# TPA3126.net
KiCad netlist of a schematic drawn in Altium Designer
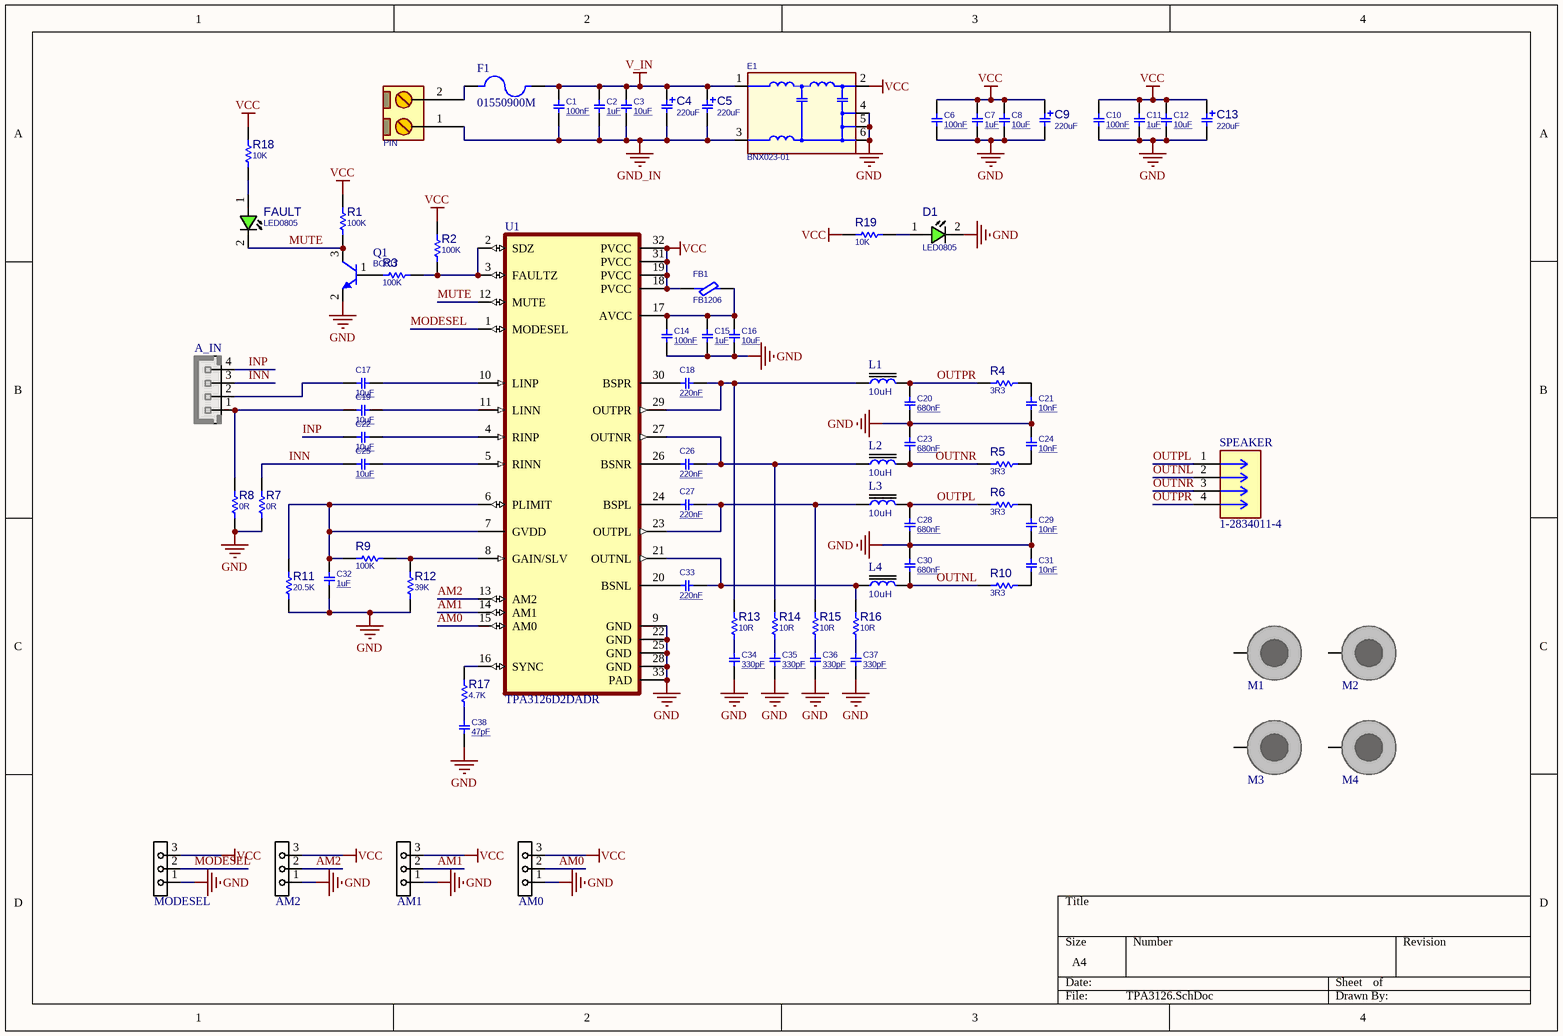
[diagram p0: TPA3126.SchDoc]

(export (version "E")
  (design (tool "Eeschema 10.0.6"))
  (components
    (comp (ref "AM0")
      (value "JMPHDR3PIN")
      (footprint "JP_3_60W")
      (description "JUMPER, HEADER 3PIN")
      (fields (field (name "MANF") "MANF") (field (name "MANF_P#") "MANF_P#"))
      (libsource (lib "test-tp_jumper") (part "JUMPER_SOLDER_3P"))
    )
    (comp (ref "AM1")
      (value "JMPHDR3PIN")
      (footprint "JP_3_60W")
      (description "JUMPER, HEADER 3PIN")
      (fields (field (name "MANF") "MANF") (field (name "MANF_P#") "MANF_P#"))
      (libsource (lib "test-tp_jumper") (part "JUMPER_SOLDER_3P"))
    )
    (comp (ref "AM2")
      (value "JMPHDR3PIN")
      (footprint "JP_3_60W")
      (description "JUMPER, HEADER 3PIN")
      (fields (field (name "MANF") "MANF") (field (name "MANF_P#") "MANF_P#"))
      (libsource (lib "test-tp_jumper") (part "JUMPER_SOLDER_3P"))
    )
    (comp (ref "A_IN")
      (value "HHDR_4")
      (footprint "XH_4")
      (description "JST-XH pitch: 2.5mm")
      (libsource (lib "conn_wire2board") (part "XH_4"))
    )
    (comp (ref "C1")
      (value "100nF")
      (footprint "C0805")
      (description "CAP, MLCC, 100nF, 50V, C0G, 10%, 0402")
      (fields (field (name "MANF_P#") "MANF_PART#") (field (name "MANF") "Murata"))
      (libsource (lib "passive_smd") (part "CAP_SMD_MLCC"))
    )
    (comp (ref "C2")
      (value "1uF")
      (footprint "C0805")
      (description "CAP, MLCC, 1uF, 50V, C0G, 10%, 0402")
      (fields (field (name "MANF_P#") "MANF_PART#") (field (name "MANF") "Murata"))
      (libsource (lib "passive_smd") (part "CAP_SMD_MLCC"))
    )
    (comp (ref "C3")
      (value "10uF")
      (footprint "C0805")
      (description "CAP, MLCC, 10uF, 50V, C0G, 10%, 0402")
      (fields (field (name "MANF_P#") "MANF_PART#") (field (name "MANF") "Murata"))
      (libsource (lib "passive_smd") (part "CAP_SMD_MLCC"))
    )
    (comp (ref "C4")
      (value "220uF")
      (footprint "C_EL_8X12")
      (description "CAP, THD, ELEC,")
      (fields (field (name "MANF_P#") "MANF_PART#") (field (name "MANF") "MANF"))
      (libsource (lib "passive_thd") (part "CAP_THD_EL"))
    )
    (comp (ref "C5")
      (value "220uF")
      (footprint "C_EL_8X12")
      (description "CAP, THD, ELEC,")
      (fields (field (name "MANF_P#") "MANF_PART#") (field (name "MANF") "MANF"))
      (libsource (lib "passive_thd") (part "CAP_THD_EL"))
    )
    (comp (ref "C6")
      (value "100nF")
      (footprint "C0805")
      (description "CAP, MLCC, 100nF, 50V, C0G, 10%, 0402")
      (fields (field (name "MANF_P#") "MANF_PART#") (field (name "MANF") "Murata"))
      (libsource (lib "passive_smd") (part "CAP_SMD_MLCC"))
    )
    (comp (ref "C7")
      (value "1uF")
      (footprint "C0805")
      (description "CAP, MLCC, 1uF, 50V, C0G, 10%, 0402")
      (fields (field (name "MANF_P#") "MANF_PART#") (field (name "MANF") "Murata"))
      (libsource (lib "passive_smd") (part "CAP_SMD_MLCC"))
    )
    (comp (ref "C8")
      (value "10uF")
      (footprint "C0805")
      (description "CAP, MLCC, 10uF, 50V, C0G, 10%, 0402")
      (fields (field (name "MANF_P#") "MANF_PART#") (field (name "MANF") "Murata"))
      (libsource (lib "passive_smd") (part "CAP_SMD_MLCC"))
    )
    (comp (ref "C9")
      (value "220uF")
      (footprint "C_EL_8X12")
      (description "CAP, THD, ELEC,")
      (fields (field (name "MANF_P#") "MANF_PART#") (field (name "MANF") "MANF"))
      (libsource (lib "passive_thd") (part "CAP_THD_EL"))
    )
    (comp (ref "C10")
      (value "100nF")
      (footprint "C0805")
      (description "CAP, MLCC, 100nF, 50V, C0G, 10%, 0402")
      (fields (field (name "MANF_P#") "MANF_PART#") (field (name "MANF") "Murata"))
      (libsource (lib "passive_smd") (part "CAP_SMD_MLCC"))
    )
    (comp (ref "C11")
      (value "1uF")
      (footprint "C0805")
      (description "CAP, MLCC, 1uF, 50V, C0G, 10%, 0402")
      (fields (field (name "MANF_P#") "MANF_PART#") (field (name "MANF") "Murata"))
      (libsource (lib "passive_smd") (part "CAP_SMD_MLCC"))
    )
    (comp (ref "C12")
      (value "10uF")
      (footprint "C0805")
      (description "CAP, MLCC, 10uF, 50V, C0G, 10%, 0402")
      (fields (field (name "MANF_P#") "MANF_PART#") (field (name "MANF") "Murata"))
      (libsource (lib "passive_smd") (part "CAP_SMD_MLCC"))
    )
    (comp (ref "C13")
      (value "220uF")
      (footprint "C_EL_8X12")
      (description "CAP, THD, ELEC,")
      (fields (field (name "MANF_P#") "MANF_PART#") (field (name "MANF") "MANF"))
      (libsource (lib "passive_thd") (part "CAP_THD_EL"))
    )
    (comp (ref "C14")
      (value "100nF")
      (footprint "C0805")
      (description "CAP, MLCC, 100nF, 50V, C0G, 10%, 0402")
      (fields (field (name "MANF_P#") "MANF_PART#") (field (name "MANF") "Murata"))
      (libsource (lib "passive_smd") (part "CAP_SMD_MLCC"))
    )
    (comp (ref "C15")
      (value "1uF")
      (footprint "C0805")
      (description "CAP, MLCC, 1uF, 50V, C0G, 10%, 0402")
      (fields (field (name "MANF_P#") "MANF_PART#") (field (name "MANF") "Murata"))
      (libsource (lib "passive_smd") (part "CAP_SMD_MLCC"))
    )
    (comp (ref "C16")
      (value "10uF")
      (footprint "C0805")
      (description "CAP, MLCC, 10uF, 50V, C0G, 10%, 0402")
      (fields (field (name "MANF_P#") "MANF_PART#") (field (name "MANF") "Murata"))
      (libsource (lib "passive_smd") (part "CAP_SMD_MLCC"))
    )
    (comp (ref "C17")
      (value "10uF")
      (footprint "C0805")
      (description "CAP, MLCC, 10uF, 50V, C0G, 10%, 0402")
      (fields (field (name "MANF_P#") "MANF_PART#") (field (name "MANF") "Murata"))
      (libsource (lib "passive_smd") (part "CAP_SMD_MLCC"))
    )
    (comp (ref "C18")
      (value "220nF")
      (footprint "C0603")
      (description "CAP, MLCC, 220nF, 50V, C0G, 10%, 0402")
      (fields (field (name "MANF_P#") "MANF_PART#") (field (name "MANF") "Murata"))
      (libsource (lib "passive_smd") (part "CAP_SMD_MLCC"))
    )
    (comp (ref "C19")
      (value "10uF")
      (footprint "C0805")
      (description "CAP, MLCC, 10uF, 50V, C0G, 10%, 0402")
      (fields (field (name "MANF_P#") "MANF_PART#") (field (name "MANF") "Murata"))
      (libsource (lib "passive_smd") (part "CAP_SMD_MLCC"))
    )
    (comp (ref "C20")
      (value "680nF")
      (footprint "C0805")
      (description "CAP, MLCC, 650nF, 50V, C0G, 10%, 0402")
      (fields (field (name "MANF_P#") "MANF_PART#") (field (name "MANF") "Murata"))
      (libsource (lib "passive_smd") (part "CAP_SMD_MLCC"))
    )
    (comp (ref "C21")
      (value "10nF")
      (footprint "C0805")
      (description "CAP, MLCC, 10nF, 50V, C0G, 10%, 0402")
      (fields (field (name "MANF_P#") "MANF_PART#") (field (name "MANF") "Murata"))
      (libsource (lib "passive_smd") (part "CAP_SMD_MLCC"))
    )
    (comp (ref "C22")
      (value "10uF")
      (footprint "C0805")
      (description "CAP, MLCC, 10uF, 50V, C0G, 10%, 0402")
      (fields (field (name "MANF_P#") "MANF_PART#") (field (name "MANF") "Murata"))
      (libsource (lib "passive_smd") (part "CAP_SMD_MLCC"))
    )
    (comp (ref "C23")
      (value "680nF")
      (footprint "C0805")
      (description "CAP, MLCC, 650nF, 50V, C0G, 10%, 0402")
      (fields (field (name "MANF_P#") "MANF_PART#") (field (name "MANF") "Murata"))
      (libsource (lib "passive_smd") (part "CAP_SMD_MLCC"))
    )
    (comp (ref "C24")
      (value "10nF")
      (footprint "C0805")
      (description "CAP, MLCC, 10nF, 50V, C0G, 10%, 0402")
      (fields (field (name "MANF_P#") "MANF_PART#") (field (name "MANF") "Murata"))
      (libsource (lib "passive_smd") (part "CAP_SMD_MLCC"))
    )
    (comp (ref "C25")
      (value "10uF")
      (footprint "C0805")
      (description "CAP, MLCC, 10uF, 50V, C0G, 10%, 0402")
      (fields (field (name "MANF_P#") "MANF_PART#") (field (name "MANF") "Murata"))
      (libsource (lib "passive_smd") (part "CAP_SMD_MLCC"))
    )
    (comp (ref "C26")
      (value "220nF")
      (footprint "C0603")
      (description "CAP, MLCC, 220nF, 50V, C0G, 10%, 0402")
      (fields (field (name "MANF_P#") "MANF_PART#") (field (name "MANF") "Murata"))
      (libsource (lib "passive_smd") (part "CAP_SMD_MLCC"))
    )
    (comp (ref "C27")
      (value "220nF")
      (footprint "C0603")
      (description "CAP, MLCC, 220nF, 50V, C0G, 10%, 0402")
      (fields (field (name "MANF_P#") "MANF_PART#") (field (name "MANF") "Murata"))
      (libsource (lib "passive_smd") (part "CAP_SMD_MLCC"))
    )
    (comp (ref "C28")
      (value "680nF")
      (footprint "C0805")
      (description "CAP, MLCC, 650nF, 50V, C0G, 10%, 0402")
      (fields (field (name "MANF_P#") "MANF_PART#") (field (name "MANF") "Murata"))
      (libsource (lib "passive_smd") (part "CAP_SMD_MLCC"))
    )
    (comp (ref "C29")
      (value "10nF")
      (footprint "C0805")
      (description "CAP, MLCC, 10nF, 50V, C0G, 10%, 0402")
      (fields (field (name "MANF_P#") "MANF_PART#") (field (name "MANF") "Murata"))
      (libsource (lib "passive_smd") (part "CAP_SMD_MLCC"))
    )
    (comp (ref "C30")
      (value "680nF")
      (footprint "C0805")
      (description "CAP, MLCC, 650nF, 50V, C0G, 10%, 0402")
      (fields (field (name "MANF_P#") "MANF_PART#") (field (name "MANF") "Murata"))
      (libsource (lib "passive_smd") (part "CAP_SMD_MLCC"))
    )
    (comp (ref "C31")
      (value "10nF")
      (footprint "C0805")
      (description "CAP, MLCC, 10nF, 50V, C0G, 10%, 0402")
      (fields (field (name "MANF_P#") "MANF_PART#") (field (name "MANF") "Murata"))
      (libsource (lib "passive_smd") (part "CAP_SMD_MLCC"))
    )
    (comp (ref "C32")
      (value "1uF")
      (footprint "C0805")
      (description "CAP, MLCC, 1uF, 50V, C0G, 10%, 0402")
      (fields (field (name "MANF_P#") "MANF_PART#") (field (name "MANF") "Murata"))
      (libsource (lib "passive_smd") (part "CAP_SMD_MLCC"))
    )
    (comp (ref "C33")
      (value "220nF")
      (footprint "C0603")
      (description "CAP, MLCC, 220nF, 50V, C0G, 10%, 0402")
      (fields (field (name "MANF_P#") "MANF_PART#") (field (name "MANF") "Murata"))
      (libsource (lib "passive_smd") (part "CAP_SMD_MLCC"))
    )
    (comp (ref "C34")
      (value "330pF")
      (footprint "C0805")
      (description "CAP, MLCC, 330pF, 50V, C0G, 10%, 0402")
      (fields (field (name "MANF_P#") "MANF_PART#") (field (name "MANF") "Murata"))
      (libsource (lib "passive_smd") (part "CAP_SMD_MLCC"))
    )
    (comp (ref "C35")
      (value "330pF")
      (footprint "C0805")
      (description "CAP, MLCC, 330pF, 50V, C0G, 10%, 0402")
      (fields (field (name "MANF_P#") "MANF_PART#") (field (name "MANF") "Murata"))
      (libsource (lib "passive_smd") (part "CAP_SMD_MLCC"))
    )
    (comp (ref "C36")
      (value "330pF")
      (footprint "C0805")
      (description "CAP, MLCC, 330pF, 50V, C0G, 10%, 0402")
      (fields (field (name "MANF_P#") "MANF_PART#") (field (name "MANF") "Murata"))
      (libsource (lib "passive_smd") (part "CAP_SMD_MLCC"))
    )
    (comp (ref "C37")
      (value "330pF")
      (footprint "C0805")
      (description "CAP, MLCC, 330pF, 50V, C0G, 10%, 0402")
      (fields (field (name "MANF_P#") "MANF_PART#") (field (name "MANF") "Murata"))
      (libsource (lib "passive_smd") (part "CAP_SMD_MLCC"))
    )
    (comp (ref "C38")
      (value "47pF")
      (footprint "C0805")
      (description "CAP, MLCC, 47pF, 50V, C0G, 10%, 0402")
      (fields (field (name "MANF_P#") "MANF_PART#") (field (name "MANF") "Murata"))
      (libsource (lib "passive_smd") (part "CAP_SMD_MLCC"))
    )
    (comp (ref "D1")
      (value "LED0805")
      (footprint "LED0805")
      (description "LED, SMD, 0805 red")
      (fields (field (name "MANF") "MANF") (field (name "MANF_P#") "MANF_PART#"))
      (libsource (lib "led(diode)") (part "LED_SMD_0805"))
    )
    (comp (ref "E1")
      (value "BNX023-01")
      (footprint "BNX02")
      (description "EMIFIL, BLOCK TYPE,")
      (fields (field (name "MANF") "Murata") (field (name "MANF_1") "MURATA"))
      (libsource (lib "emi_filter") (part "BNX023-01"))
    )
    (comp (ref "F1")
      (value "01550900M")
      (footprint "FUSE_01550900M")
      (description "Fuse Block, Cartridge, OMNI-BLOK Series, 125V, 10A, J-Lead ¦ Littelfuse 01550900M")
      (fields (field (name "MF") "Littelfuse Inc."))
      (libsource (lib "01550900M") (part "01550900M"))
    )
    (comp (ref "FAULT")
      (value "LED0805")
      (footprint "LED0805")
      (description "LED, SMD, 0805 red")
      (fields (field (name "MANF") "MANF") (field (name "MANF_P#") "MANF_PART#"))
      (libsource (lib "led(diode)") (part "LED_SMD_0805"))
    )
    (comp (ref "FB1")
      (value "FB1206")
      (footprint "L1206")
      (description "FERRITE_Bead, SMD")
      (fields (field (name "MANF") "MURATA") (field (name "MANF_P#") "BLM15AG121SN1D"))
      (libsource (lib "emi_filter") (part "FBEAD_SMD"))
    )
    (comp (ref "L1")
      (value "10uH")
      (footprint "L_12")
      (description "INDUCTOR, POWER, SMD")
      (libsource (lib "inductor_power") (part "INDPWR_SMD"))
    )
    (comp (ref "L2")
      (value "10uH")
      (footprint "L_12")
      (description "INDUCTOR, POWER, SMD")
      (libsource (lib "inductor_power") (part "INDPWR_SMD"))
    )
    (comp (ref "L3")
      (value "10uH")
      (footprint "L_12")
      (description "INDUCTOR, POWER, SMD")
      (libsource (lib "inductor_power") (part "INDPWR_SMD"))
    )
    (comp (ref "L4")
      (value "10uH")
      (footprint "L_12")
      (description "INDUCTOR, POWER, SMD")
      (libsource (lib "inductor_power") (part "INDPWR_SMD"))
    )
    (comp (ref "M1")
      (value "DNP/MH")
      (footprint "SCMH_M3P5FT")
      (description "SCREW mouting, M3.5, 3.5mm diameter and 7.0mm, FlatHead")
      (libsource (lib "mech_mountingHole") (part "SCMH_M3P5FT"))
    )
    (comp (ref "M2")
      (value "DNP/MH")
      (footprint "SCMH_M3P5FT")
      (description "SCREW mouting, M3.5, 3.5mm diameter and 7.0mm, FlatHead")
      (libsource (lib "mech_mountingHole") (part "SCMH_M3P5FT"))
    )
    (comp (ref "M3")
      (value "DNP/MH")
      (footprint "SCMH_M3P5FT")
      (description "SCREW mouting, M3.5, 3.5mm diameter and 7.0mm, FlatHead")
      (libsource (lib "mech_mountingHole") (part "SCMH_M3P5FT"))
    )
    (comp (ref "M4")
      (value "DNP/MH")
      (footprint "SCMH_M3P5FT")
      (description "SCREW mouting, M3.5, 3.5mm diameter and 7.0mm, FlatHead")
      (libsource (lib "mech_mountingHole") (part "SCMH_M3P5FT"))
    )
    (comp (ref "MODESEL")
      (value "JMPHDR3PIN")
      (footprint "JP_3_60W")
      (description "JUMPER, HEADER 3PIN")
      (fields (field (name "MANF") "MANF") (field (name "MANF_P#") "MANF_P#"))
      (libsource (lib "test-tp_jumper") (part "JUMPER_SOLDER_3P"))
    )
    (comp (ref "PIN")
      (value "CONN_TB2")
      (footprint "MSTB_2")
      (description "CONN, PHOENIX MSTB, 5-G, 5.08mm pitch")
      (libsource (lib "conn_power_terminalB") (part "CONN_MSTB_2"))
    )
    (comp (ref "Q1")
      (value "BC817")
      (footprint "SOT23_3")
      (description "BJT, NPN, 45v, 0.5A, SMD, SOT23")
      (fields (field (name "MANF") "NXP, ON"))
      (libsource (lib "transistor_bjt") (part "NPN_BC817_SOT23"))
    )
    (comp (ref "R1")
      (value "100K")
      (footprint "R0805")
      (description "RESISTOR, SMD")
      (libsource (lib "passive_smd") (part "RES_SMD"))
    )
    (comp (ref "R2")
      (value "100K")
      (footprint "R0805")
      (description "RESISTOR, SMD")
      (libsource (lib "passive_smd") (part "RES_SMD"))
    )
    (comp (ref "R3")
      (value "100K")
      (footprint "R0805")
      (description "RESISTOR, SMD")
      (libsource (lib "passive_smd") (part "RES_SMD"))
    )
    (comp (ref "R4")
      (value "3R3")
      (footprint "R0805")
      (description "RESISTOR, SMD")
      (libsource (lib "passive_smd") (part "RES_SMD"))
    )
    (comp (ref "R5")
      (value "3R3")
      (footprint "R0805")
      (description "RESISTOR, SMD")
      (libsource (lib "passive_smd") (part "RES_SMD"))
    )
    (comp (ref "R6")
      (value "3R3")
      (footprint "R0805")
      (description "RESISTOR, SMD")
      (libsource (lib "passive_smd") (part "RES_SMD"))
    )
    (comp (ref "R7")
      (value "0R")
      (footprint "R0805")
      (description "RESISTOR, SMD")
      (libsource (lib "passive_smd") (part "RES_SMD"))
    )
    (comp (ref "R8")
      (value "0R")
      (footprint "R0805")
      (description "RESISTOR, SMD")
      (libsource (lib "passive_smd") (part "RES_SMD"))
    )
    (comp (ref "R9")
      (value "100K")
      (footprint "R0805")
      (description "RESISTOR, SMD")
      (libsource (lib "passive_smd") (part "RES_SMD"))
    )
    (comp (ref "R10")
      (value "3R3")
      (footprint "R0805")
      (description "RESISTOR, SMD")
      (libsource (lib "passive_smd") (part "RES_SMD"))
    )
    (comp (ref "R11")
      (value "20.5K")
      (footprint "R0805")
      (description "RESISTOR, SMD")
      (libsource (lib "passive_smd") (part "RES_SMD"))
    )
    (comp (ref "R12")
      (value "39K")
      (footprint "R0805")
      (description "RESISTOR, SMD")
      (libsource (lib "passive_smd") (part "RES_SMD"))
    )
    (comp (ref "R13")
      (value "10R")
      (footprint "R0805")
      (description "RESISTOR, SMD")
      (libsource (lib "passive_smd") (part "RES_SMD"))
    )
    (comp (ref "R14")
      (value "10R")
      (footprint "R0805")
      (description "RESISTOR, SMD")
      (libsource (lib "passive_smd") (part "RES_SMD"))
    )
    (comp (ref "R15")
      (value "10R")
      (footprint "R0805")
      (description "RESISTOR, SMD")
      (libsource (lib "passive_smd") (part "RES_SMD"))
    )
    (comp (ref "R16")
      (value "10R")
      (footprint "R0805")
      (description "RESISTOR, SMD")
      (libsource (lib "passive_smd") (part "RES_SMD"))
    )
    (comp (ref "R17")
      (value "4.7K")
      (footprint "R0805")
      (description "RESISTOR, SMD")
      (libsource (lib "passive_smd") (part "RES_SMD"))
    )
    (comp (ref "R18")
      (value "10K")
      (footprint "R0805")
      (description "RESISTOR, SMD")
      (libsource (lib "passive_smd") (part "RES_SMD"))
    )
    (comp (ref "R19")
      (value "10K")
      (footprint "R0805")
      (description "RESISTOR, SMD")
      (libsource (lib "passive_smd") (part "RES_SMD"))
    )
    (comp (ref "SPEAKER")
      (value "1-2834011-4")
      (footprint "CONN_1-2834011-4")
      (libsource (lib "WJ250") (part "1-2834011-4"))
    )
    (comp (ref "U1")
      (value "TPA3126D2DADR")
      (footprint "SOP65P810X115-33N")
      (libsource (lib "amp_audio") (part "TPA3126D2DADR"))
    )
  )
  (nets
    (net (code "1") (name "/AM0") (class "Default")
      (node (ref "AM0") (pin "2") (pinfunction "2_2") (pintype "passive"))
      (node (ref "U1") (pin "15") (pinfunction "AM0_15") (pintype "bidirectional"))
    )
    (net (code "2") (name "/AM1") (class "Default")
      (node (ref "AM1") (pin "2") (pinfunction "2_2") (pintype "passive"))
      (node (ref "U1") (pin "14") (pinfunction "AM1_14") (pintype "bidirectional"))
    )
    (net (code "3") (name "/AM2") (class "Default")
      (node (ref "AM2") (pin "2") (pinfunction "2_2") (pintype "passive"))
      (node (ref "U1") (pin "13") (pinfunction "AM2_13") (pintype "bidirectional"))
    )
    (net (code "4") (name "/INN") (class "Default")
      (node (ref "A_IN") (pin "3") (pinfunction "3_3") (pintype "passive"))
      (node (ref "C25") (pin "1") (pinfunction "1_1") (pintype "passive"))
      (node (ref "R7") (pin "1") (pinfunction "1_1") (pintype "passive"))
    )
    (net (code "5") (name "/INP") (class "Default")
      (node (ref "A_IN") (pin "4") (pinfunction "4_4") (pintype "passive"))
      (node (ref "C22") (pin "1") (pinfunction "1_1") (pintype "passive"))
    )
    (net (code "6") (name "/MODESEL") (class "Default")
      (node (ref "MODESEL") (pin "2") (pinfunction "2_2") (pintype "passive"))
      (node (ref "U1") (pin "1") (pinfunction "MODESEL_1") (pintype "bidirectional"))
    )
    (net (code "7") (name "/MUTE") (class "Default")
      (node (ref "FAULT") (pin "2") (pinfunction "CATHODE_2") (pintype "passive"))
      (node (ref "Q1") (pin "3") (pinfunction "C_3") (pintype "passive"))
      (node (ref "R1") (pin "1") (pinfunction "1_1") (pintype "passive"))
      (node (ref "U1") (pin "12") (pinfunction "MUTE_12") (pintype "bidirectional"))
    )
    (net (code "8") (name "/OUTNL") (class "Default")
      (node (ref "C30") (pin "2") (pinfunction "2_2") (pintype "passive"))
      (node (ref "L4") (pin "2") (pinfunction "2_2") (pintype "passive"))
      (node (ref "R10") (pin "2") (pinfunction "2_2") (pintype "passive"))
      (node (ref "SPEAKER") (pin "2") (pinfunction "2_2") (pintype "passive"))
    )
    (net (code "9") (name "/OUTNR") (class "Default")
      (node (ref "C23") (pin "2") (pinfunction "2_2") (pintype "passive"))
      (node (ref "L2") (pin "2") (pinfunction "2_2") (pintype "passive"))
      (node (ref "R5") (pin "2") (pinfunction "2_2") (pintype "passive"))
      (node (ref "SPEAKER") (pin "3") (pinfunction "3_3") (pintype "passive"))
    )
    (net (code "10") (name "/OUTPL") (class "Default")
      (node (ref "C28") (pin "1") (pinfunction "1_1") (pintype "passive"))
      (node (ref "L3") (pin "2") (pinfunction "2_2") (pintype "passive"))
      (node (ref "R6") (pin "2") (pinfunction "2_2") (pintype "passive"))
      (node (ref "SPEAKER") (pin "1") (pinfunction "1_1") (pintype "passive"))
    )
    (net (code "11") (name "/OUTPR") (class "Default")
      (node (ref "C20") (pin "1") (pinfunction "1_1") (pintype "passive"))
      (node (ref "L1") (pin "2") (pinfunction "2_2") (pintype "passive"))
      (node (ref "R4") (pin "2") (pinfunction "2_2") (pintype "passive"))
      (node (ref "SPEAKER") (pin "4") (pinfunction "4_4") (pintype "passive"))
    )
    (net (code "12") (name "GND") (class "Default")
      (node (ref "AM0") (pin "1") (pinfunction "1_1") (pintype "passive"))
      (node (ref "AM1") (pin "1") (pinfunction "1_1") (pintype "passive"))
      (node (ref "AM2") (pin "1") (pinfunction "1_1") (pintype "passive"))
      (node (ref "C10") (pin "2") (pinfunction "2_2") (pintype "passive"))
      (node (ref "C11") (pin "2") (pinfunction "2_2") (pintype "passive"))
      (node (ref "C12") (pin "2") (pinfunction "2_2") (pintype "passive"))
      (node (ref "C13") (pin "2") (pinfunction "2_2") (pintype "passive"))
      (node (ref "C14") (pin "2") (pinfunction "2_2") (pintype "passive"))
      (node (ref "C15") (pin "2") (pinfunction "2_2") (pintype "passive"))
      (node (ref "C16") (pin "2") (pinfunction "2_2") (pintype "passive"))
      (node (ref "C20") (pin "2") (pinfunction "2_2") (pintype "passive"))
      (node (ref "C21") (pin "1") (pinfunction "1_1") (pintype "passive"))
      (node (ref "C23") (pin "1") (pinfunction "1_1") (pintype "passive"))
      (node (ref "C24") (pin "2") (pinfunction "2_2") (pintype "passive"))
      (node (ref "C28") (pin "2") (pinfunction "2_2") (pintype "passive"))
      (node (ref "C29") (pin "1") (pinfunction "1_1") (pintype "passive"))
      (node (ref "C30") (pin "1") (pinfunction "1_1") (pintype "passive"))
      (node (ref "C31") (pin "2") (pinfunction "2_2") (pintype "passive"))
      (node (ref "C32") (pin "2") (pinfunction "2_2") (pintype "passive"))
      (node (ref "C34") (pin "2") (pinfunction "2_2") (pintype "passive"))
      (node (ref "C35") (pin "2") (pinfunction "2_2") (pintype "passive"))
      (node (ref "C36") (pin "2") (pinfunction "2_2") (pintype "passive"))
      (node (ref "C37") (pin "2") (pinfunction "2_2") (pintype "passive"))
      (node (ref "C38") (pin "2") (pinfunction "2_2") (pintype "passive"))
      (node (ref "C6") (pin "2") (pinfunction "2_2") (pintype "passive"))
      (node (ref "C7") (pin "2") (pinfunction "2_2") (pintype "passive"))
      (node (ref "C8") (pin "2") (pinfunction "2_2") (pintype "passive"))
      (node (ref "C9") (pin "2") (pinfunction "2_2") (pintype "passive"))
      (node (ref "D1") (pin "2") (pinfunction "CATHODE_2") (pintype "passive"))
      (node (ref "E1") (pin "4") (pinfunction "CG1_4") (pintype "passive"))
      (node (ref "E1") (pin "5") (pinfunction "CG2_5") (pintype "passive"))
      (node (ref "E1") (pin "6") (pinfunction "CG3_6") (pintype "passive"))
      (node (ref "MODESEL") (pin "1") (pinfunction "1_1") (pintype "passive"))
      (node (ref "Q1") (pin "2") (pinfunction "E_2") (pintype "passive"))
      (node (ref "R11") (pin "2") (pinfunction "2_2") (pintype "passive"))
      (node (ref "R12") (pin "2") (pinfunction "2_2") (pintype "passive"))
      (node (ref "R7") (pin "2") (pinfunction "2_2") (pintype "passive"))
      (node (ref "R8") (pin "2") (pinfunction "2_2") (pintype "passive"))
      (node (ref "U1") (pin "22") (pinfunction "GND_22") (pintype "power_in"))
      (node (ref "U1") (pin "25") (pinfunction "GND_25") (pintype "power_in"))
      (node (ref "U1") (pin "28") (pinfunction "GND_28") (pintype "power_in"))
      (node (ref "U1") (pin "33") (pinfunction "PAD_33") (pintype "power_in"))
      (node (ref "U1") (pin "9") (pinfunction "GND_9") (pintype "power_in"))
    )
    (net (code "13") (name "GND_IN") (class "Default")
      (node (ref "C1") (pin "2") (pinfunction "2_2") (pintype "passive"))
      (node (ref "C2") (pin "2") (pinfunction "2_2") (pintype "passive"))
      (node (ref "C3") (pin "2") (pinfunction "2_2") (pintype "passive"))
      (node (ref "C4") (pin "2") (pinfunction "2_2") (pintype "passive"))
      (node (ref "C5") (pin "2") (pinfunction "2_2") (pintype "passive"))
      (node (ref "E1") (pin "3") (pinfunction "PSG_3") (pintype "passive"))
      (node (ref "PIN") (pin "1") (pinfunction "1_1") (pintype "passive"))
    )
    (net (code "14") (name "Net-(A_IN-Pad1)") (class "Default")
      (node (ref "A_IN") (pin "1") (pinfunction "1_1") (pintype "passive"))
      (node (ref "C19") (pin "1") (pinfunction "1_1") (pintype "passive"))
      (node (ref "R8") (pin "1") (pinfunction "1_1") (pintype "passive"))
    )
    (net (code "15") (name "Net-(A_IN-Pad2)") (class "Default")
      (node (ref "A_IN") (pin "2") (pinfunction "2_2") (pintype "passive"))
      (node (ref "C17") (pin "1") (pinfunction "1_1") (pintype "passive"))
    )
    (net (code "16") (name "Net-(C21-Pad2)") (class "Default")
      (node (ref "C21") (pin "2") (pinfunction "2_2") (pintype "passive"))
      (node (ref "R4") (pin "1") (pinfunction "1_1") (pintype "passive"))
    )
    (net (code "17") (name "Net-(C24-Pad1)") (class "Default")
      (node (ref "C24") (pin "1") (pinfunction "1_1") (pintype "passive"))
      (node (ref "R5") (pin "1") (pinfunction "1_1") (pintype "passive"))
    )
    (net (code "18") (name "Net-(C29-Pad2)") (class "Default")
      (node (ref "C29") (pin "2") (pinfunction "2_2") (pintype "passive"))
      (node (ref "R6") (pin "1") (pinfunction "1_1") (pintype "passive"))
    )
    (net (code "19") (name "Net-(C31-Pad1)") (class "Default")
      (node (ref "C31") (pin "1") (pinfunction "1_1") (pintype "passive"))
      (node (ref "R10") (pin "1") (pinfunction "1_1") (pintype "passive"))
    )
    (net (code "20") (name "Net-(C34-Pad1)") (class "Default")
      (node (ref "C34") (pin "1") (pinfunction "1_1") (pintype "passive"))
      (node (ref "R13") (pin "1") (pinfunction "1_1") (pintype "passive"))
    )
    (net (code "21") (name "Net-(C35-Pad1)") (class "Default")
      (node (ref "C35") (pin "1") (pinfunction "1_1") (pintype "passive"))
      (node (ref "R14") (pin "1") (pinfunction "1_1") (pintype "passive"))
    )
    (net (code "22") (name "Net-(C36-Pad1)") (class "Default")
      (node (ref "C36") (pin "1") (pinfunction "1_1") (pintype "passive"))
      (node (ref "R15") (pin "1") (pinfunction "1_1") (pintype "passive"))
    )
    (net (code "23") (name "Net-(C37-Pad1)") (class "Default")
      (node (ref "C37") (pin "1") (pinfunction "1_1") (pintype "passive"))
      (node (ref "R16") (pin "1") (pinfunction "1_1") (pintype "passive"))
    )
    (net (code "24") (name "Net-(C38-Pad1)") (class "Default")
      (node (ref "C38") (pin "1") (pinfunction "1_1") (pintype "passive"))
      (node (ref "R17") (pin "1") (pinfunction "1_1") (pintype "passive"))
    )
    (net (code "25") (name "Net-(D1-ANODE)") (class "Default")
      (node (ref "D1") (pin "1") (pinfunction "ANODE_1") (pintype "passive"))
      (node (ref "R19") (pin "2") (pinfunction "2_2") (pintype "passive"))
    )
    (net (code "26") (name "Net-(F1-Pad1)") (class "Default")
      (node (ref "F1") (pin "1") (pinfunction "1_1") (pintype "passive"))
      (node (ref "PIN") (pin "2") (pinfunction "2_2") (pintype "passive"))
    )
    (net (code "27") (name "Net-(FAULT-ANODE)") (class "Default")
      (node (ref "FAULT") (pin "1") (pinfunction "ANODE_1") (pintype "passive"))
      (node (ref "R18") (pin "2") (pinfunction "2_2") (pintype "passive"))
    )
    (net (code "28") (name "Net-(Q1-B)") (class "Default")
      (node (ref "Q1") (pin "1") (pinfunction "B_1") (pintype "passive"))
      (node (ref "R3") (pin "2") (pinfunction "2_2") (pintype "passive"))
    )
    (net (code "29") (name "Net-(U1-AVCC)") (class "Default")
      (node (ref "C14") (pin "1") (pinfunction "1_1") (pintype "passive"))
      (node (ref "C15") (pin "1") (pinfunction "1_1") (pintype "passive"))
      (node (ref "C16") (pin "1") (pinfunction "1_1") (pintype "passive"))
      (node (ref "FB1") (pin "1") (pinfunction "1_1") (pintype "passive"))
      (node (ref "U1") (pin "17") (pinfunction "AVCC_17") (pintype "power_in"))
    )
    (net (code "30") (name "Net-(U1-BSNL)") (class "Default")
      (node (ref "C33") (pin "1") (pinfunction "1_1") (pintype "passive"))
      (node (ref "U1") (pin "20") (pinfunction "BSNL_20") (pintype "power_in"))
    )
    (net (code "31") (name "Net-(U1-BSNR)") (class "Default")
      (node (ref "C26") (pin "1") (pinfunction "1_1") (pintype "passive"))
      (node (ref "U1") (pin "26") (pinfunction "BSNR_26") (pintype "power_in"))
    )
    (net (code "32") (name "Net-(U1-BSPL)") (class "Default")
      (node (ref "C27") (pin "1") (pinfunction "1_1") (pintype "passive"))
      (node (ref "U1") (pin "24") (pinfunction "BSPL_24") (pintype "power_in"))
    )
    (net (code "33") (name "Net-(U1-BSPR)") (class "Default")
      (node (ref "C18") (pin "1") (pinfunction "1_1") (pintype "passive"))
      (node (ref "U1") (pin "30") (pinfunction "BSPR_30") (pintype "power_in"))
    )
    (net (code "34") (name "Net-(U1-FAULTZ)") (class "Default")
      (node (ref "R2") (pin "1") (pinfunction "1_1") (pintype "passive"))
      (node (ref "R3") (pin "1") (pinfunction "1_1") (pintype "passive"))
      (node (ref "U1") (pin "2") (pinfunction "SDZ_2") (pintype "bidirectional"))
      (node (ref "U1") (pin "3") (pinfunction "FAULTZ_3") (pintype "bidirectional"))
    )
    (net (code "35") (name "Net-(U1-GAIN{slash}SLV)") (class "Default")
      (node (ref "R12") (pin "1") (pinfunction "1_1") (pintype "passive"))
      (node (ref "R9") (pin "2") (pinfunction "2_2") (pintype "passive"))
      (node (ref "U1") (pin "8") (pinfunction "GAIN/SLV_8") (pintype "input"))
    )
    (net (code "36") (name "Net-(U1-GVDD)") (class "Default")
      (node (ref "C32") (pin "1") (pinfunction "1_1") (pintype "passive"))
      (node (ref "R11") (pin "1") (pinfunction "1_1") (pintype "passive"))
      (node (ref "R9") (pin "1") (pinfunction "1_1") (pintype "passive"))
      (node (ref "U1") (pin "6") (pinfunction "PLIMIT_6") (pintype "bidirectional"))
      (node (ref "U1") (pin "7") (pinfunction "GVDD_7") (pintype "power_in"))
    )
    (net (code "37") (name "Net-(U1-LINN)") (class "Default")
      (node (ref "C19") (pin "2") (pinfunction "2_2") (pintype "passive"))
      (node (ref "U1") (pin "11") (pinfunction "LINN_11") (pintype "input"))
    )
    (net (code "38") (name "Net-(U1-LINP)") (class "Default")
      (node (ref "C17") (pin "2") (pinfunction "2_2") (pintype "passive"))
      (node (ref "U1") (pin "10") (pinfunction "LINP_10") (pintype "input"))
    )
    (net (code "39") (name "Net-(U1-OUTNL)") (class "Default")
      (node (ref "C33") (pin "2") (pinfunction "2_2") (pintype "passive"))
      (node (ref "L4") (pin "1") (pinfunction "1_1") (pintype "passive"))
      (node (ref "R16") (pin "2") (pinfunction "2_2") (pintype "passive"))
      (node (ref "U1") (pin "21") (pinfunction "OUTNL_21") (pintype "output"))
    )
    (net (code "40") (name "Net-(U1-OUTNR)") (class "Default")
      (node (ref "C26") (pin "2") (pinfunction "2_2") (pintype "passive"))
      (node (ref "L2") (pin "1") (pinfunction "1_1") (pintype "passive"))
      (node (ref "R14") (pin "2") (pinfunction "2_2") (pintype "passive"))
      (node (ref "U1") (pin "27") (pinfunction "OUTNR_27") (pintype "output"))
    )
    (net (code "41") (name "Net-(U1-OUTPL)") (class "Default")
      (node (ref "C27") (pin "2") (pinfunction "2_2") (pintype "passive"))
      (node (ref "L3") (pin "1") (pinfunction "1_1") (pintype "passive"))
      (node (ref "R15") (pin "2") (pinfunction "2_2") (pintype "passive"))
      (node (ref "U1") (pin "23") (pinfunction "OUTPL_23") (pintype "output"))
    )
    (net (code "42") (name "Net-(U1-OUTPR)") (class "Default")
      (node (ref "C18") (pin "2") (pinfunction "2_2") (pintype "passive"))
      (node (ref "L1") (pin "1") (pinfunction "1_1") (pintype "passive"))
      (node (ref "R13") (pin "2") (pinfunction "2_2") (pintype "passive"))
      (node (ref "U1") (pin "29") (pinfunction "OUTPR_29") (pintype "output"))
    )
    (net (code "43") (name "Net-(U1-RINN)") (class "Default")
      (node (ref "C25") (pin "2") (pinfunction "2_2") (pintype "passive"))
      (node (ref "U1") (pin "5") (pinfunction "RINN_5") (pintype "input"))
    )
    (net (code "44") (name "Net-(U1-RINP)") (class "Default")
      (node (ref "C22") (pin "2") (pinfunction "2_2") (pintype "passive"))
      (node (ref "U1") (pin "4") (pinfunction "RINP_4") (pintype "input"))
    )
    (net (code "45") (name "Net-(U1-SYNC)") (class "Default")
      (node (ref "R17") (pin "2") (pinfunction "2_2") (pintype "passive"))
      (node (ref "U1") (pin "16") (pinfunction "SYNC_16") (pintype "bidirectional"))
    )
    (net (code "46") (name "VCC") (class "Default")
      (node (ref "AM0") (pin "3") (pinfunction "3_3") (pintype "passive"))
      (node (ref "AM1") (pin "3") (pinfunction "3_3") (pintype "passive"))
      (node (ref "AM2") (pin "3") (pinfunction "3_3") (pintype "passive"))
      (node (ref "C10") (pin "1") (pinfunction "1_1") (pintype "passive"))
      (node (ref "C11") (pin "1") (pinfunction "1_1") (pintype "passive"))
      (node (ref "C12") (pin "1") (pinfunction "1_1") (pintype "passive"))
      (node (ref "C13") (pin "1") (pinfunction "1_1") (pintype "passive"))
      (node (ref "C6") (pin "1") (pinfunction "1_1") (pintype "passive"))
      (node (ref "C7") (pin "1") (pinfunction "1_1") (pintype "passive"))
      (node (ref "C8") (pin "1") (pinfunction "1_1") (pintype "passive"))
      (node (ref "C9") (pin "1") (pinfunction "1_1") (pintype "passive"))
      (node (ref "E1") (pin "2") (pinfunction "CB_2") (pintype "passive"))
      (node (ref "FB1") (pin "2") (pinfunction "2_2") (pintype "passive"))
      (node (ref "MODESEL") (pin "3") (pinfunction "3_3") (pintype "passive"))
      (node (ref "R1") (pin "2") (pinfunction "2_2") (pintype "passive"))
      (node (ref "R18") (pin "1") (pinfunction "1_1") (pintype "passive"))
      (node (ref "R19") (pin "1") (pinfunction "1_1") (pintype "passive"))
      (node (ref "R2") (pin "2") (pinfunction "2_2") (pintype "passive"))
      (node (ref "U1") (pin "18") (pinfunction "PVCC_18") (pintype "power_in"))
      (node (ref "U1") (pin "19") (pinfunction "PVCC_19") (pintype "power_in"))
      (node (ref "U1") (pin "31") (pinfunction "PVCC_31") (pintype "power_in"))
      (node (ref "U1") (pin "32") (pinfunction "PVCC_32") (pintype "power_in"))
    )
    (net (code "47") (name "V_IN") (class "Default")
      (node (ref "C1") (pin "1") (pinfunction "1_1") (pintype "passive"))
      (node (ref "C2") (pin "1") (pinfunction "1_1") (pintype "passive"))
      (node (ref "C3") (pin "1") (pinfunction "1_1") (pintype "passive"))
      (node (ref "C4") (pin "1") (pinfunction "1_1") (pintype "passive"))
      (node (ref "C5") (pin "1") (pinfunction "1_1") (pintype "passive"))
      (node (ref "E1") (pin "1") (pinfunction "B_1") (pintype "passive"))
      (node (ref "F1") (pin "2") (pinfunction "2_2") (pintype "passive"))
    )
    (net (code "48") (name "unconnected-(M1-Pad1)") (class "Default")
      (node (ref "M1") (pin "1") (pinfunction "1_1") (pintype "passive"))
    )
    (net (code "49") (name "unconnected-(M2-Pad1)") (class "Default")
      (node (ref "M2") (pin "1") (pinfunction "1_1") (pintype "passive"))
    )
    (net (code "50") (name "unconnected-(M3-Pad1)") (class "Default")
      (node (ref "M3") (pin "1") (pinfunction "1_1") (pintype "passive"))
    )
    (net (code "51") (name "unconnected-(M4-Pad1)") (class "Default")
      (node (ref "M4") (pin "1") (pinfunction "1_1") (pintype "passive"))
    )
  )
)
